# Sensor_Glove_Pheripherals-X02.net
KiCad netlist of a schematic drawn in Altium Designer
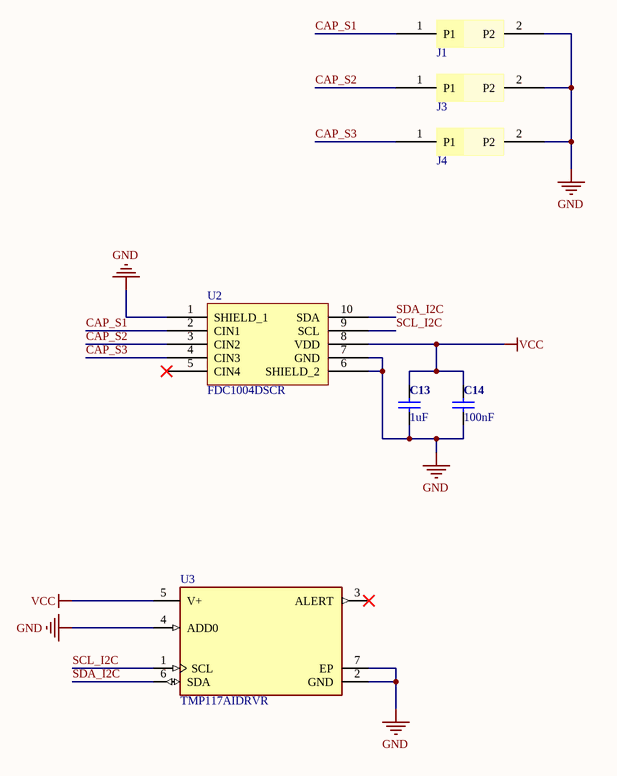
[diagram p0: Sensor_Glove_Pheripherals-X02.SchDoc]

(export (version "E")
  (design (tool "Eeschema 10.0.6"))
  (components
    (comp (ref "C13")
      (value "1uF")
      (footprint "C0402")
      (fields
        (field (name "MANUFACTURER") "Yageo")
        (field (name "MANUFACTURER PART NUMBER") "CC0402MRX5R5BB105")
        (field (name "TOLERANCE") "20%")
      )
      (libsource (lib "DB-X02") (part "C-0402(1005)"))
    )
    (comp (ref "C14")
      (value "100nF")
      (footprint "C0402")
      (fields
        (field (name "MANUFACTURER") "Taiyo Yuden")
        (field (name "MANUFACTURER PART NUMBER") "TMK105BJ104KV-F")
        (field (name "TOLERANCE") "10%")
      )
      (libsource (lib "DB-X02") (part "C-0402(1005)"))
    )
    (comp (ref "J1")
      (value "Sensor Interconnect Pads")
      (footprint "Sensor_Interconnect_Pad")
      (description "Hole Pads for sensor interconnect solder pads")
      (libsource (lib "Sensor_Glove-X02") (part "Sensor_Interconnect"))
    )
    (comp (ref "J3")
      (value "Sensor Interconnect Pads")
      (footprint "Sensor_Interconnect_Pad")
      (description "Hole Pads for sensor interconnect solder pads")
      (libsource (lib "Sensor_Glove-X02") (part "Sensor_Interconnect"))
    )
    (comp (ref "J4")
      (value "Sensor Interconnect Pads")
      (footprint "Sensor_Interconnect_Pad")
      (description "Hole Pads for sensor interconnect solder pads")
      (libsource (lib "Sensor_Glove-X02") (part "Sensor_Interconnect"))
    )
    (comp (ref "U2")
      (value "4 CHANNEL CDC")
      (footprint "WSON-10 3X3MM")
      (description "Analog Circuit, 1 Func, 4 Channel, PDSO10")
      (fields
        (field (name "MANUFACTURER") "Texas Instruments")
        (field (name "MANUFACTURER PART NUMBER") "FDC1004DSCR")
      )
      (libsource (lib "DB-X02") (part "FDC1004"))
    )
    (comp (ref "U3")
      (value "TMP117AIDRVR")
      (footprint "TMP117AIDRVR")
      (description "TEMPERATURE SENSOR")
      (fields
        (field (name "OCTOPART") "https://octopart.com/tmp117aidrvr-texas+instruments-95511044")
        (field (name "MANUFACTURER") "Texas Instruments")
      )
      (libsource (lib "DB-X01") (part "bceab6869a9cb85cf5675529ee35ce4"))
    )
  )
  (nets
    (net (code "1") (name "/CAP_S1") (class "Default")
      (node (ref "J1") (pin "1") (pinfunction "P1_1") (pintype "passive"))
      (node (ref "U2") (pin "2") (pinfunction "CIN1_2") (pintype "passive"))
    )
    (net (code "2") (name "/CAP_S2") (class "Default")
      (node (ref "J3") (pin "1") (pinfunction "P1_1") (pintype "passive"))
      (node (ref "U2") (pin "3") (pinfunction "CIN2_3") (pintype "passive"))
    )
    (net (code "3") (name "/CAP_S3") (class "Default")
      (node (ref "J4") (pin "1") (pinfunction "P1_1") (pintype "passive"))
      (node (ref "U2") (pin "4") (pinfunction "CIN3_4") (pintype "passive"))
    )
    (net (code "4") (name "/SCL_I2C") (class "Default")
      (node (ref "U2") (pin "9") (pinfunction "SCL_9") (pintype "passive"))
      (node (ref "U3") (pin "1") (pinfunction "SCL_1") (pintype "input"))
    )
    (net (code "5") (name "/SDA_I2C") (class "Default")
      (node (ref "U2") (pin "10") (pinfunction "SDA_10") (pintype "passive"))
      (node (ref "U3") (pin "6") (pinfunction "SDA_6") (pintype "bidirectional"))
    )
    (net (code "6") (name "GND") (class "Default")
      (node (ref "C13") (pin "2") (pinfunction "2_2") (pintype "passive"))
      (node (ref "C14") (pin "2") (pinfunction "2_2") (pintype "passive"))
      (node (ref "J1") (pin "2") (pinfunction "P2_2") (pintype "passive"))
      (node (ref "J3") (pin "2") (pinfunction "P2_2") (pintype "passive"))
      (node (ref "J4") (pin "2") (pinfunction "P2_2") (pintype "passive"))
      (node (ref "U2") (pin "1") (pinfunction "SHIELD_1_1") (pintype "passive"))
      (node (ref "U2") (pin "6") (pinfunction "SHIELD_2_6") (pintype "passive"))
      (node (ref "U2") (pin "7") (pinfunction "GND_7") (pintype "passive"))
      (node (ref "U3") (pin "2") (pinfunction "GND_2") (pintype "power_in"))
      (node (ref "U3") (pin "4") (pinfunction "ADD0_4") (pintype "input"))
      (node (ref "U3") (pin "7") (pinfunction "EP_7") (pintype "passive"))
    )
    (net (code "7") (name "VCC") (class "Default")
      (node (ref "C13") (pin "1") (pinfunction "1_1") (pintype "passive"))
      (node (ref "C14") (pin "1") (pinfunction "1_1") (pintype "passive"))
      (node (ref "U2") (pin "8") (pinfunction "VDD_8") (pintype "passive"))
      (node (ref "U3") (pin "5") (pinfunction "V+_5") (pintype "power_in"))
    )
    (net (code "8") (name "unconnected-(U2-CIN4-Pad5)") (class "Default")
      (node (ref "U2") (pin "5") (pinfunction "CIN4_5") (pintype "passive+no_connect"))
    )
    (net (code "9") (name "unconnected-(U3-ALERT-Pad3)") (class "Default")
      (node (ref "U3") (pin "3") (pinfunction "ALERT_3") (pintype "output+no_connect"))
    )
  )
)
